# PLD_LMT87.net
KiCad netlist of a schematic drawn in Altium Designer
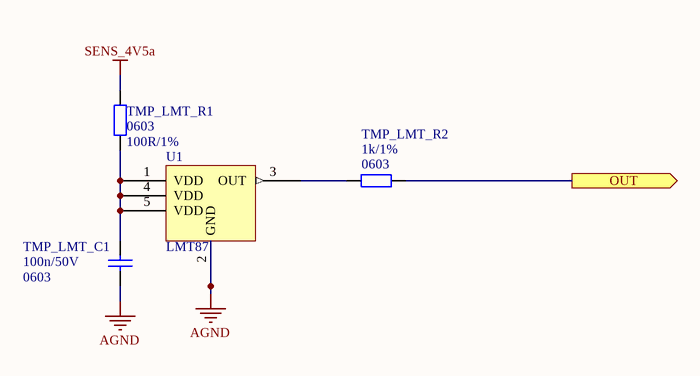
[diagram p0: PLD_LMT87.SchDoc]

(export (version "E")
  (design (tool "Eeschema 10.0.6"))
  (components
    (comp (ref "TMP_LMT_C1")
      (value "100n/50V")
      (footprint "SMD_Capacitor_0603")
      (description "Ceramic Cap Kemet COTS 100n/50V X7R 0603")
      (fields
        (field (name "MANUFACTURER") "Kemet")
        (field (name "MANUFACTURERPARTNUMBER") "C0603T104K5RALTU")
        (field (name "PACKAGE") "0603")
      )
      (libsource (lib "capacitors") (part "Cer_C0603T104K5RALTU"))
    )
    (comp (ref "TMP_LMT_R1")
      (value "100R/1%")
      (footprint "SMD_Resistor_0603")
      (description "100R/1% Vishay CRCW 0603 Resistor. 100mW, 100ppm, 75V.")
      (fields
        (field (name "MANUFACTURER") "Vishay")
        (field (name "MANUFACTURERPARTNUMBER") "CRCW0603100RFKxxxx")
        (field (name "PACKAGE") "0603")
      )
      (libsource (lib "resistors") (part "CRCW0603100RFKxxxx"))
    )
    (comp (ref "TMP_LMT_R2")
      (value "1k/1%")
      (footprint "SMD_Resistor_0603")
      (description "1k/1% Vishay CRCW 0603 Resistor. 100mW, 100ppm, 75V.")
      (fields
        (field (name "MANUFACTURER") "Vishay")
        (field (name "MANUFACTURERPARTNUMBER") "CRCW06031K00FKxxxx")
        (field (name "PACKAGE") "0603")
      )
      (libsource (lib "resistors") (part "CRCW06031K00FKxxxx"))
    )
    (comp (ref "U1")
      (value "LMT87")
      (footprint "SC70-LT5_N")
      (description "Analog Temperature Sensors with Class-AB Output")
      (libsource (lib "microcircuits") (part "LMT87"))
    )
  )
  (nets
    (net (code "1") (name "/OUT") (class "Default")
      (node (ref "TMP_LMT_R2") (pin "2") (pinfunction "2_2") (pintype "passive"))
    )
    (net (code "2") (name "AGND") (class "Default")
      (node (ref "TMP_LMT_C1") (pin "2") (pinfunction "2_2") (pintype "passive"))
      (node (ref "U1") (pin "2") (pinfunction "GND_2") (pintype "power_in"))
    )
    (net (code "3") (name "Net-(TMP_LMT_C1-Pad1)") (class "Default")
      (node (ref "TMP_LMT_C1") (pin "1") (pinfunction "1_1") (pintype "passive"))
      (node (ref "TMP_LMT_R1") (pin "1") (pinfunction "1_1") (pintype "passive"))
      (node (ref "U1") (pin "1") (pinfunction "VDD_1") (pintype "passive"))
      (node (ref "U1") (pin "4") (pinfunction "VDD_4") (pintype "power_in"))
      (node (ref "U1") (pin "5") (pinfunction "VDD_5") (pintype "power_in"))
    )
    (net (code "4") (name "Net-(U1-OUT)") (class "Default")
      (node (ref "TMP_LMT_R2") (pin "1") (pinfunction "1_1") (pintype "passive"))
      (node (ref "U1") (pin "3") (pinfunction "OUT_3") (pintype "output"))
    )
    (net (code "5") (name "SENS_4V5a") (class "Default")
      (node (ref "TMP_LMT_R1") (pin "2") (pinfunction "2_2") (pintype "passive"))
    )
  )
)
